# untitled.net
KiCad netlist of a schematic drawn in EAGLE
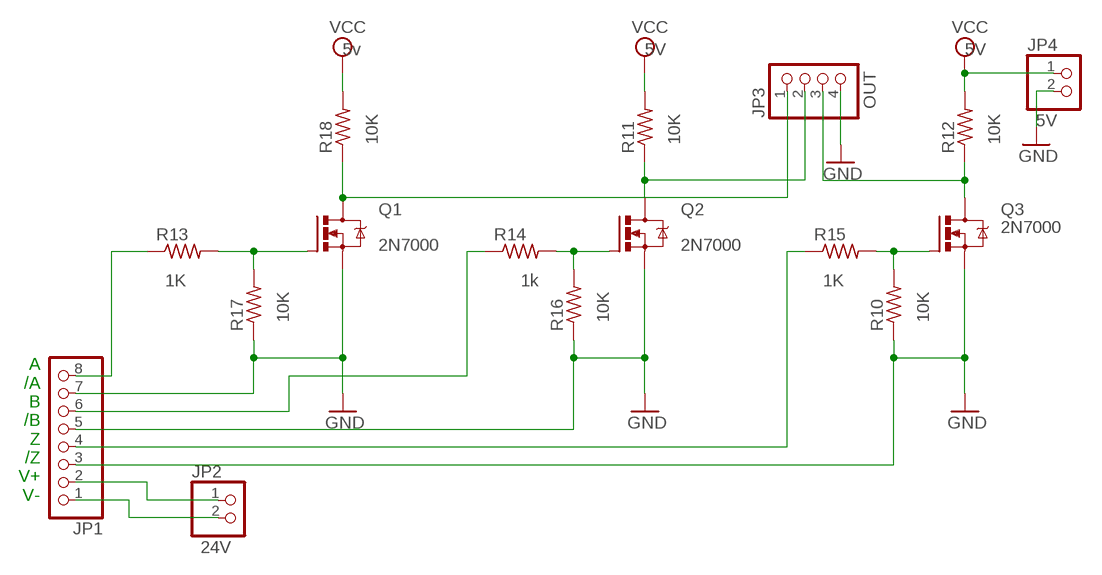
[diagram p0: schematic, sheet 1]

(export (version "E")
  (design (tool "Eeschema 10.0.6"))
  (components
    (comp (ref "JP1")
      (value "PINHD-1X8")
      (footprint "eagle-import:1X08")
      (libsource (lib "eagle-import") (part "PINHD-1X8"))
    )
    (comp (ref "JP2")
      (value "PINHD-1X2")
      (footprint "eagle-import:1X02")
      (libsource (lib "eagle-import") (part "PINHD-1X2"))
    )
    (comp (ref "JP3")
      (value "PINHD-1X4")
      (footprint "eagle-import:1X04")
      (libsource (lib "eagle-import") (part "PINHD-1X4"))
    )
    (comp (ref "JP4")
      (value "PINHD-1X2")
      (footprint "eagle-import:1X02")
      (libsource (lib "eagle-import") (part "PINHD-1X2"))
    )
    (comp (ref "Q1")
      (value "IRF540")
      (footprint "eagle-import:TO220BV")
      (libsource (lib "eagle-import") (part "IRF540"))
    )
    (comp (ref "Q2")
      (value "IRF540")
      (footprint "eagle-import:TO220BV")
      (libsource (lib "eagle-import") (part "IRF540"))
    )
    (comp (ref "Q3")
      (value "IRF540")
      (footprint "eagle-import:TO220BV")
      (libsource (lib "eagle-import") (part "IRF540"))
    )
    (comp (ref "R10")
      (value "R-US_M0805")
      (footprint "eagle-import:M0805")
      (libsource (lib "eagle-import") (part "R-US_M0805"))
    )
    (comp (ref "R11")
      (value "R-US_M0805")
      (footprint "eagle-import:M0805")
      (libsource (lib "eagle-import") (part "R-US_M0805"))
    )
    (comp (ref "R12")
      (value "R-US_M0805")
      (footprint "eagle-import:M0805")
      (libsource (lib "eagle-import") (part "R-US_M0805"))
    )
    (comp (ref "R13")
      (value "R-US_M0805")
      (footprint "eagle-import:M0805")
      (fields (field (name "SPICEPREFIX") "R") (field (name "SPICEPREFIX_1") "1K"))
      (libsource (lib "eagle-import") (part "R-US_M0805"))
    )
    (comp (ref "R14")
      (value "R-US_M0805")
      (footprint "eagle-import:M0805")
      (fields (field (name "SPICEPREFIX") "R") (field (name "SPICEPREFIX_1") "1k"))
      (libsource (lib "eagle-import") (part "R-US_M0805"))
    )
    (comp (ref "R15")
      (value "R-US_M0805")
      (footprint "eagle-import:M0805")
      (fields (field (name "SPICEPREFIX") "R") (field (name "SPICEPREFIX_1") "1K"))
      (libsource (lib "eagle-import") (part "R-US_M0805"))
    )
    (comp (ref "R16")
      (value "R-US_M0805")
      (footprint "eagle-import:M0805")
      (libsource (lib "eagle-import") (part "R-US_M0805"))
    )
    (comp (ref "R17")
      (value "R-US_M0805")
      (footprint "eagle-import:M0805")
      (libsource (lib "eagle-import") (part "R-US_M0805"))
    )
    (comp (ref "R18")
      (value "R-US_M0805")
      (footprint "eagle-import:M0805")
      (fields (field (name "10K") "10K"))
      (libsource (lib "eagle-import") (part "R-US_M0805"))
    )
  )
  (nets
    (net (code "1") (name "GND") (class "Default")
      (node (ref "JP1") (pin "3") (pinfunction "3_3") (pintype "passive"))
      (node (ref "JP1") (pin "5") (pinfunction "5_5") (pintype "passive"))
      (node (ref "JP1") (pin "7") (pinfunction "7_7") (pintype "passive"))
      (node (ref "JP3") (pin "4") (pinfunction "4_4") (pintype "passive"))
      (node (ref "JP4") (pin "2") (pinfunction "2_2") (pintype "passive"))
      (node (ref "Q1") (pin "S") (pinfunction "S_S") (pintype "passive"))
      (node (ref "Q2") (pin "S") (pinfunction "S_S") (pintype "passive"))
      (node (ref "Q3") (pin "S") (pinfunction "S_S") (pintype "passive"))
      (node (ref "R10") (pin "1") (pinfunction "1_1") (pintype "passive"))
      (node (ref "R16") (pin "1") (pinfunction "1_1") (pintype "passive"))
      (node (ref "R17") (pin "1") (pinfunction "1_1") (pintype "passive"))
    )
    (net (code "2") (name "Net-(JP1-Pad1)") (class "Default")
      (node (ref "JP1") (pin "1") (pinfunction "1_1") (pintype "passive"))
      (node (ref "JP2") (pin "2") (pinfunction "2_2") (pintype "passive"))
    )
    (net (code "3") (name "Net-(JP1-Pad2)") (class "Default")
      (node (ref "JP1") (pin "2") (pinfunction "2_2") (pintype "passive"))
      (node (ref "JP2") (pin "1") (pinfunction "1_1") (pintype "passive"))
    )
    (net (code "4") (name "Net-(JP1-Pad4)") (class "Default")
      (node (ref "JP1") (pin "4") (pinfunction "4_4") (pintype "passive"))
      (node (ref "R15") (pin "1") (pinfunction "1_1") (pintype "passive"))
    )
    (net (code "5") (name "Net-(JP1-Pad6)") (class "Default")
      (node (ref "JP1") (pin "6") (pinfunction "6_6") (pintype "passive"))
      (node (ref "R14") (pin "1") (pinfunction "1_1") (pintype "passive"))
    )
    (net (code "6") (name "Net-(JP1-Pad8)") (class "Default")
      (node (ref "JP1") (pin "8") (pinfunction "8_8") (pintype "passive"))
      (node (ref "R13") (pin "1") (pinfunction "1_1") (pintype "passive"))
    )
    (net (code "7") (name "Net-(JP3-Pad1)") (class "Default")
      (node (ref "JP3") (pin "1") (pinfunction "1_1") (pintype "passive"))
      (node (ref "Q1") (pin "D") (pinfunction "D_D") (pintype "passive"))
      (node (ref "R18") (pin "1") (pinfunction "1_1") (pintype "passive"))
    )
    (net (code "8") (name "Net-(JP3-Pad2)") (class "Default")
      (node (ref "JP3") (pin "2") (pinfunction "2_2") (pintype "passive"))
      (node (ref "Q2") (pin "D") (pinfunction "D_D") (pintype "passive"))
      (node (ref "R11") (pin "1") (pinfunction "1_1") (pintype "passive"))
    )
    (net (code "9") (name "Net-(JP3-Pad3)") (class "Default")
      (node (ref "JP3") (pin "3") (pinfunction "3_3") (pintype "passive"))
      (node (ref "Q3") (pin "D") (pinfunction "D_D") (pintype "passive"))
      (node (ref "R12") (pin "1") (pinfunction "1_1") (pintype "passive"))
    )
    (net (code "10") (name "Net-(Q1-PadG)") (class "Default")
      (node (ref "Q1") (pin "G") (pinfunction "G_G") (pintype "passive"))
      (node (ref "R13") (pin "2") (pinfunction "2_2") (pintype "passive"))
      (node (ref "R17") (pin "2") (pinfunction "2_2") (pintype "passive"))
    )
    (net (code "11") (name "Net-(Q2-PadG)") (class "Default")
      (node (ref "Q2") (pin "G") (pinfunction "G_G") (pintype "passive"))
      (node (ref "R14") (pin "2") (pinfunction "2_2") (pintype "passive"))
      (node (ref "R16") (pin "2") (pinfunction "2_2") (pintype "passive"))
    )
    (net (code "12") (name "Net-(Q3-PadG)") (class "Default")
      (node (ref "Q3") (pin "G") (pinfunction "G_G") (pintype "passive"))
      (node (ref "R10") (pin "2") (pinfunction "2_2") (pintype "passive"))
      (node (ref "R15") (pin "2") (pinfunction "2_2") (pintype "passive"))
    )
    (net (code "13") (name "VCC") (class "Default")
      (node (ref "JP4") (pin "1") (pinfunction "1_1") (pintype "passive"))
      (node (ref "R11") (pin "2") (pinfunction "2_2") (pintype "passive"))
      (node (ref "R12") (pin "2") (pinfunction "2_2") (pintype "passive"))
      (node (ref "R18") (pin "2") (pinfunction "2_2") (pintype "passive"))
    )
  )
)
